# 07-AD9546_Outputs.net
KiCad netlist of a schematic drawn in Altium Designer
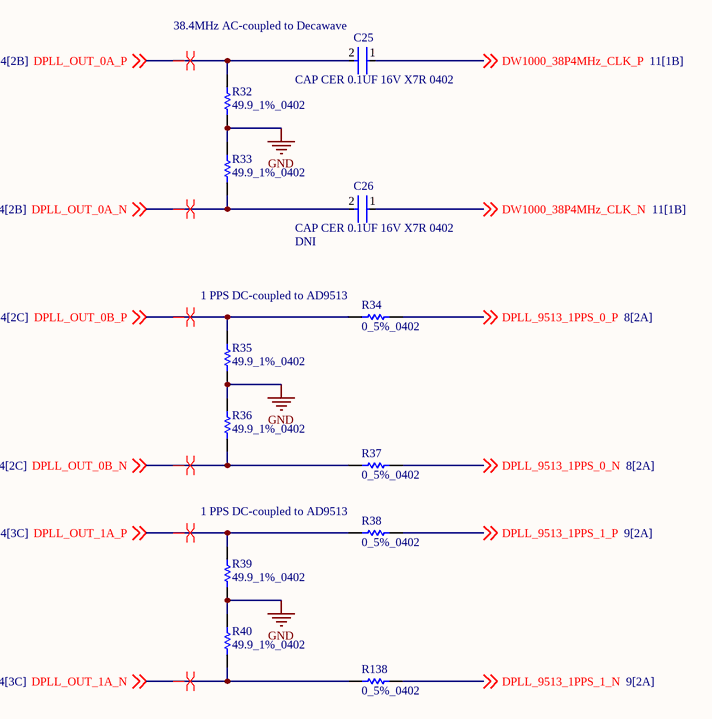
[diagram p0: 07-AD9546_Outputs.SchDoc]

(export (version "E")
  (design (tool "Eeschema 10.0.6"))
  (components
    (comp (ref "C25")
      (value "GRM155R71C104KA88D")
      (footprint "FP-GRM15-MFG")
      (description "CAP CER 0.1UF 16V X7R 0402")
      (fields
        (field (name "TOLERANCE") "10%")
        (field (name "OCTOPART") "https://octopart.com/grm155r71c104ka88d-murata-196880")
        (field (name "DIGIKEY DESCRIPTION") "CAP CER 0.1UF 16V X7R 0402")
      )
      (libsource (lib "Altium Content Vault") (part "236180d848d6139a670b325ea6854c9"))
    )
    (comp (ref "C26")
      (value "GRM155R71C104KA88D")
      (footprint "FP-GRM15-MFG")
      (description "CAP CER 0.1UF 16V X7R 0402")
      (fields
        (field (name "TOLERANCE") "10%")
        (field (name "OCTOPART") "https://octopart.com/grm155r71c104ka88d-murata-196880")
        (field (name "DIGIKEY DESCRIPTION") "CAP CER 0.1UF 16V X7R 0402")
        (field (name "DNI") "DNI")
      )
      (libsource (lib "Altium Content Vault") (part "236180d848d6139a670b325ea6854c9"))
    )
    (comp (ref "R32")
      (value "49.9_1%_0402")
      (footprint "RESC1005X40X25NL05T05")
      (fields (field (name "MANUFACTURER") "Panasonic") (field (name "PART NUMBER") "ERJ-2RKF49R9X"))
      (libsource (lib "Altium Content Vault") (part "RES"))
    )
    (comp (ref "R33")
      (value "49.9_1%_0402")
      (footprint "RESC1005X40X25NL05T05")
      (fields (field (name "MANUFACTURER") "Panasonic") (field (name "PART NUMBER") "ERJ-2RKF49R9X"))
      (libsource (lib "Altium Content Vault") (part "RES"))
    )
    (comp (ref "R34")
      (value "0_5%_0402")
      (footprint "RESC1005X40X25LL10T10")
      (fields (field (name "MANUFACTURER") "KOA Speer") (field (name "PART NUMBER") "RK73Z1ETTP"))
      (libsource (lib "Altium Content Vault") (part "RES"))
    )
    (comp (ref "R35")
      (value "49.9_1%_0402")
      (footprint "RESC1005X40X25NL05T05")
      (fields (field (name "MANUFACTURER") "Panasonic") (field (name "PART NUMBER") "ERJ-2RKF49R9X"))
      (libsource (lib "Altium Content Vault") (part "RES"))
    )
    (comp (ref "R36")
      (value "49.9_1%_0402")
      (footprint "RESC1005X40X25NL05T05")
      (fields (field (name "MANUFACTURER") "Panasonic") (field (name "PART NUMBER") "ERJ-2RKF49R9X"))
      (libsource (lib "Altium Content Vault") (part "RES"))
    )
    (comp (ref "R37")
      (value "0_5%_0402")
      (footprint "RESC1005X40X25LL10T10")
      (fields (field (name "MANUFACTURER") "KOA Speer") (field (name "PART NUMBER") "RK73Z1ETTP"))
      (libsource (lib "Altium Content Vault") (part "RES"))
    )
    (comp (ref "R38")
      (value "0_5%_0402")
      (footprint "RESC1005X40X25LL10T10")
      (fields (field (name "MANUFACTURER") "KOA Speer") (field (name "PART NUMBER") "RK73Z1ETTP"))
      (libsource (lib "Altium Content Vault") (part "RES"))
    )
    (comp (ref "R39")
      (value "49.9_1%_0402")
      (footprint "RESC1005X40X25NL05T05")
      (fields (field (name "MANUFACTURER") "Panasonic") (field (name "PART NUMBER") "ERJ-2RKF49R9X"))
      (libsource (lib "Altium Content Vault") (part "RES"))
    )
    (comp (ref "R40")
      (value "49.9_1%_0402")
      (footprint "RESC1005X40X25NL05T05")
      (fields (field (name "MANUFACTURER") "Panasonic") (field (name "PART NUMBER") "ERJ-2RKF49R9X"))
      (libsource (lib "Altium Content Vault") (part "RES"))
    )
    (comp (ref "R138")
      (value "0_5%_0402")
      (footprint "RESC1005X40X25LL10T10")
      (fields (field (name "MANUFACTURER") "KOA Speer") (field (name "PART NUMBER") "RK73Z1ETTP"))
      (libsource (lib "Altium Content Vault") (part "RES"))
    )
  )
  (nets
    (net (code "1") (name "DPLL_9513_1PPS_0_N") (class "Default")
      (node (ref "R37") (pin "2") (pinfunction "2_2") (pintype "passive"))
    )
    (net (code "2") (name "DPLL_9513_1PPS_0_P") (class "Default")
      (node (ref "R34") (pin "2") (pinfunction "2_2") (pintype "passive"))
    )
    (net (code "3") (name "DPLL_9513_1PPS_1_N") (class "Default")
      (node (ref "R138") (pin "2") (pinfunction "2_2") (pintype "passive"))
    )
    (net (code "4") (name "DPLL_9513_1PPS_1_P") (class "Default")
      (node (ref "R38") (pin "2") (pinfunction "2_2") (pintype "passive"))
    )
    (net (code "5") (name "DPLL_OUT_0A_N") (class "Default")
      (node (ref "C26") (pin "2") (pinfunction "2_2") (pintype "passive"))
      (node (ref "R33") (pin "1") (pinfunction "1_1") (pintype "passive"))
    )
    (net (code "6") (name "DPLL_OUT_0A_P") (class "Default")
      (node (ref "C25") (pin "2") (pinfunction "2_2") (pintype "passive"))
      (node (ref "R32") (pin "2") (pinfunction "2_2") (pintype "passive"))
    )
    (net (code "7") (name "DPLL_OUT_0B_N") (class "Default")
      (node (ref "R36") (pin "1") (pinfunction "1_1") (pintype "passive"))
      (node (ref "R37") (pin "1") (pinfunction "1_1") (pintype "passive"))
    )
    (net (code "8") (name "DPLL_OUT_0B_P") (class "Default")
      (node (ref "R34") (pin "1") (pinfunction "1_1") (pintype "passive"))
      (node (ref "R35") (pin "2") (pinfunction "2_2") (pintype "passive"))
    )
    (net (code "9") (name "DPLL_OUT_1A_N") (class "Default")
      (node (ref "R138") (pin "1") (pinfunction "1_1") (pintype "passive"))
      (node (ref "R40") (pin "1") (pinfunction "1_1") (pintype "passive"))
    )
    (net (code "10") (name "DPLL_OUT_1A_P") (class "Default")
      (node (ref "R38") (pin "1") (pinfunction "1_1") (pintype "passive"))
      (node (ref "R39") (pin "2") (pinfunction "2_2") (pintype "passive"))
    )
    (net (code "11") (name "DW1000_38P4MHz_CLK_N") (class "Default")
      (node (ref "C26") (pin "1") (pinfunction "1_1") (pintype "passive"))
    )
    (net (code "12") (name "DW1000_38P4MHz_CLK_P") (class "Default")
      (node (ref "C25") (pin "1") (pinfunction "1_1") (pintype "passive"))
    )
    (net (code "13") (name "GND") (class "Default")
      (node (ref "R32") (pin "1") (pinfunction "1_1") (pintype "passive"))
      (node (ref "R33") (pin "2") (pinfunction "2_2") (pintype "passive"))
      (node (ref "R35") (pin "1") (pinfunction "1_1") (pintype "passive"))
      (node (ref "R36") (pin "2") (pinfunction "2_2") (pintype "passive"))
      (node (ref "R39") (pin "1") (pinfunction "1_1") (pintype "passive"))
      (node (ref "R40") (pin "2") (pinfunction "2_2") (pintype "passive"))
    )
  )
)
